# design.net
KiCad netlist of a schematic drawn in Altium Designer
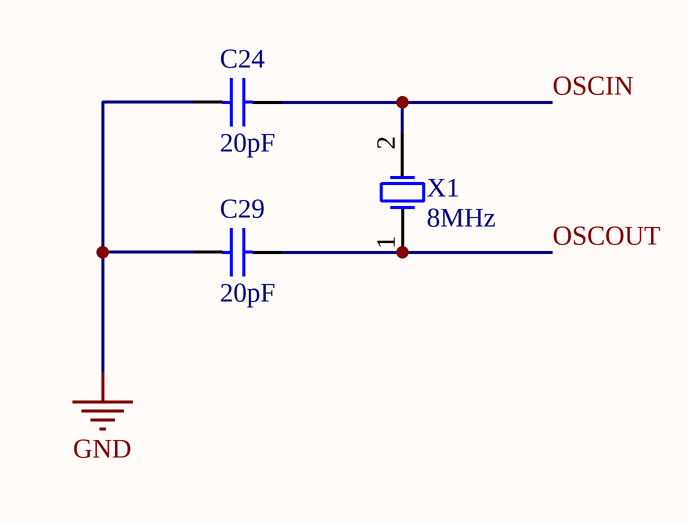
[diagram p0: 晶振.SchDoc]

(export (version "E")
  (design (tool "Eeschema 10.0.6"))
  (components
    (comp (ref "C24")
      (value "20pF")
      (footprint "LC-0805_C")
      (description "100nF��0805��50V,+/-10%")
      (libsource (lib "ECG") (part "Cap"))
    )
    (comp (ref "C29")
      (value "20pF")
      (footprint "LC-0805_C")
      (description "100nF��0805��50V,+/-10%")
      (libsource (lib "ECG") (part "Cap"))
    )
    (comp (ref "X1")
      (value "8MHz")
      (footprint "XTAL_US")
      (description "8MHz����49S")
      (libsource (lib "ECG") (part "XTAL"))
    )
  )
  (nets
    (net (code "1") (name "/OSCIN") (class "Default")
      (node (ref "C24") (pin "2") (pinfunction "2_2") (pintype "passive"))
      (node (ref "X1") (pin "2") (pinfunction "OSC2_2") (pintype "passive"))
    )
    (net (code "2") (name "/OSCOUT") (class "Default")
      (node (ref "C29") (pin "2") (pinfunction "2_2") (pintype "passive"))
      (node (ref "X1") (pin "1") (pinfunction "OSC1_1") (pintype "passive"))
    )
    (net (code "3") (name "GND") (class "Default")
      (node (ref "C24") (pin "1") (pinfunction "1_1") (pintype "passive"))
      (node (ref "C29") (pin "1") (pinfunction "1_1") (pintype "passive"))
    )
  )
)
